# Sensor_module.net
KiCad netlist of a schematic drawn in EAGLE
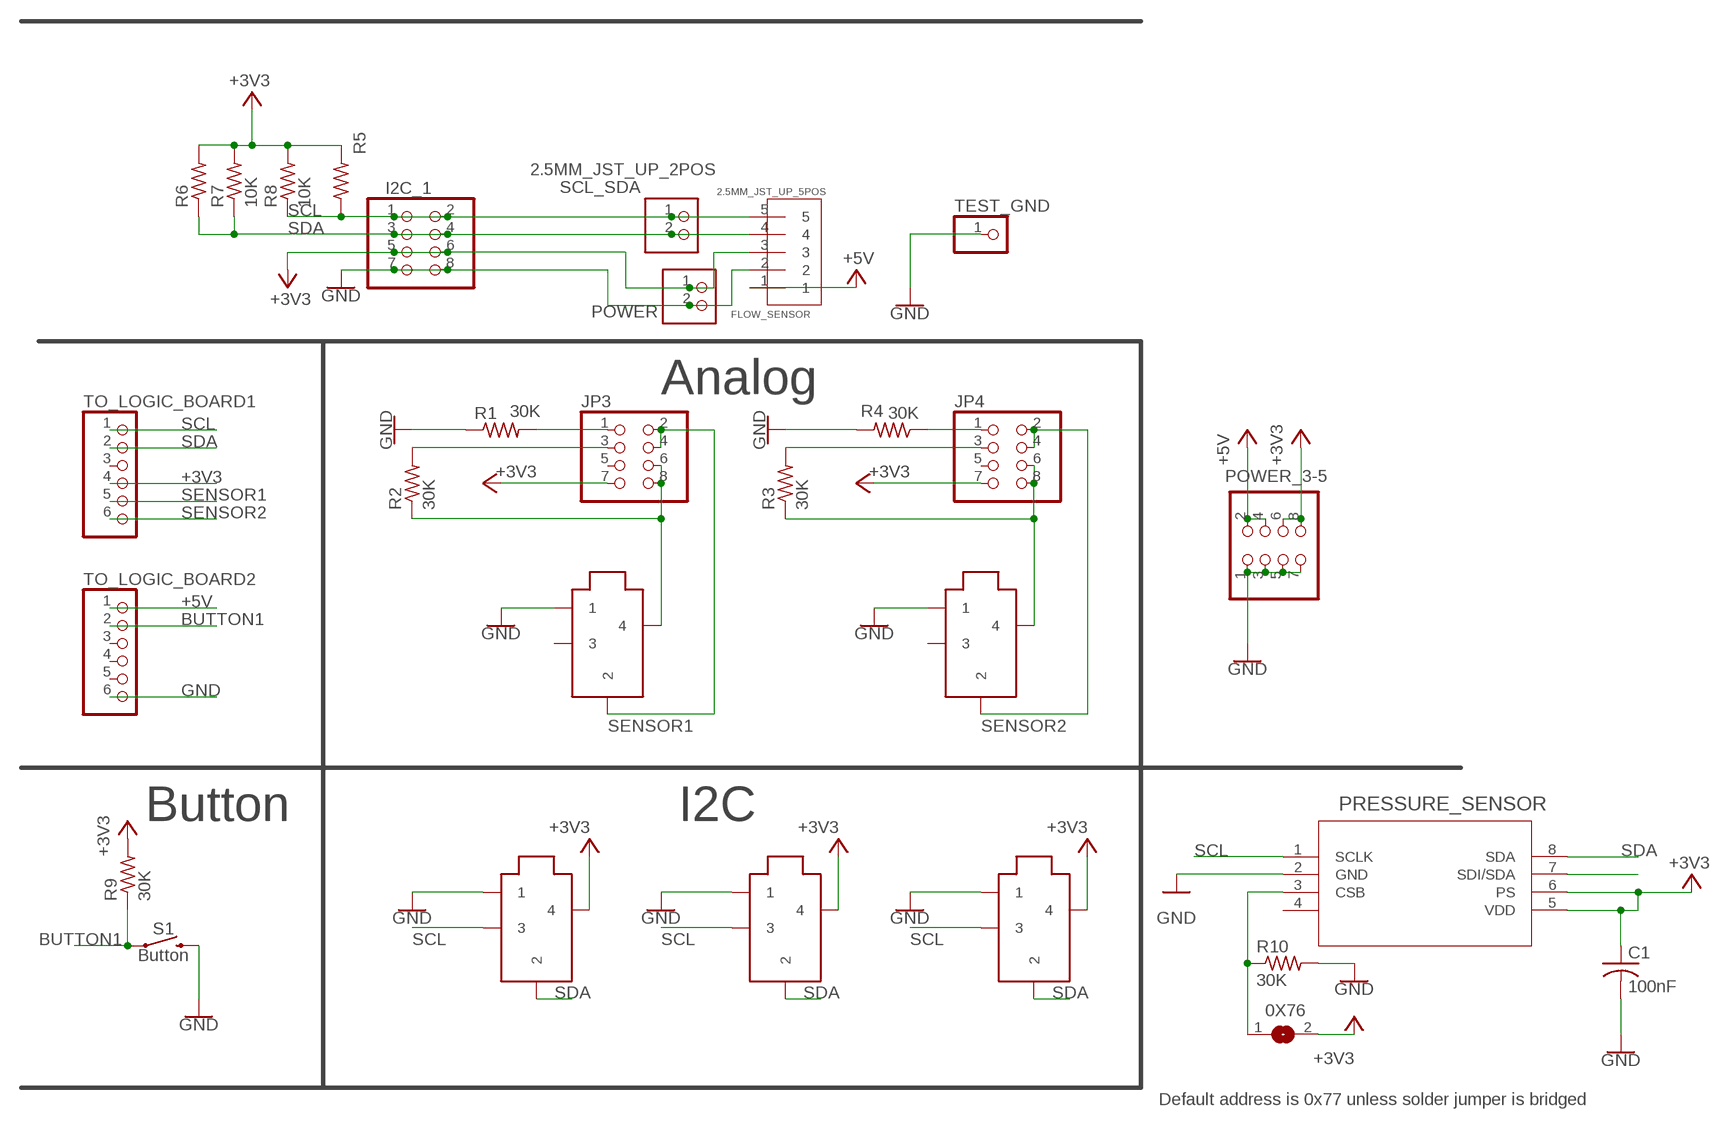
[diagram p0: schematic, sheet 1]

(export (version "E")
  (design (tool "Eeschema 10.0.6"))
  (components
    (comp (ref "0X76")
      (value "SJ")
      (footprint "eagle-import:SJ")
      (libsource (lib "eagle-import") (part "SJ"))
    )
    (comp (ref "ANALOG1")
      (value "AUDIOJACK_2.5MM_SMD")
      (footprint "eagle-import:AJ_2.5_SMD")
      (libsource (lib "eagle-import") (part "AUDIOJACK_2.5MM_SMD"))
    )
    (comp (ref "ANALOG2")
      (value "AUDIOJACK_2.5MM_SMD")
      (footprint "eagle-import:AJ_2.5_SMD")
      (libsource (lib "eagle-import") (part "AUDIOJACK_2.5MM_SMD"))
    )
    (comp (ref "C1")
      (value "100nF")
      (footprint "eagle-import:C1206")
      (libsource (lib "eagle-import") (part "C-USC1206"))
    )
    (comp (ref "FLOW_SENSOR")
      (value "2.5MM_JST_UP_5POS")
      (footprint "eagle-import:JST_5POS_2.5MM_UP")
      (libsource (lib "eagle-import") (part "2.5MM_JST_UP_5POS"))
    )
    (comp (ref "I2C_1")
      (value "PINHD-2X4")
      (footprint "eagle-import:2X04")
      (libsource (lib "eagle-import") (part "PINHD-2X4"))
    )
    (comp (ref "JP3")
      (value "PINHD-2X4")
      (footprint "eagle-import:2X04")
      (libsource (lib "eagle-import") (part "PINHD-2X4"))
    )
    (comp (ref "JP4")
      (value "PINHD-2X4")
      (footprint "eagle-import:2X04")
      (libsource (lib "eagle-import") (part "PINHD-2X4"))
    )
    (comp (ref "POWER")
      (value "2.5MM_JST_UP_2POS")
      (footprint "eagle-import:JST_2POS_2.5MM_UP")
      (libsource (lib "eagle-import") (part "2.5MM_JST_UP_2POS"))
    )
    (comp (ref "POWER_3-5")
      (value "PINHD-2X4")
      (footprint "eagle-import:2X04")
      (libsource (lib "eagle-import") (part "PINHD-2X4"))
    )
    (comp (ref "PRESSURE_SENSOR")
      (value "MS580302BA01-00")
      (footprint "eagle-import:MS5803-02BA01")
      (fields (field (name "MANUFACTURER_PART_NUMBER") "MS580302BA0100"))
      (libsource (lib "eagle-import") (part "MS580302BA01-00"))
    )
    (comp (ref "R1")
      (value "30K")
      (footprint "eagle-import:R1206")
      (libsource (lib "eagle-import") (part "R-US_R1206"))
    )
    (comp (ref "R2")
      (value "30K")
      (footprint "eagle-import:R1206")
      (libsource (lib "eagle-import") (part "R-US_R1206"))
    )
    (comp (ref "R3")
      (value "30K")
      (footprint "eagle-import:R1206")
      (libsource (lib "eagle-import") (part "R-US_R1206"))
    )
    (comp (ref "R4")
      (value "30K")
      (footprint "eagle-import:R1206")
      (libsource (lib "eagle-import") (part "R-US_R1206"))
    )
    (comp (ref "R5")
      (value "R-US_R1206")
      (footprint "eagle-import:R1206")
      (libsource (lib "eagle-import") (part "R-US_R1206"))
    )
    (comp (ref "R6")
      (value "R-US_R1206")
      (footprint "eagle-import:R1206")
      (libsource (lib "eagle-import") (part "R-US_R1206"))
    )
    (comp (ref "R7")
      (value "10K")
      (footprint "eagle-import:0204_7")
      (libsource (lib "eagle-import") (part "R-US_0204/7"))
    )
    (comp (ref "R8")
      (value "10K")
      (footprint "eagle-import:0204_7")
      (libsource (lib "eagle-import") (part "R-US_0204/7"))
    )
    (comp (ref "R9")
      (value "30K")
      (footprint "eagle-import:R1206")
      (libsource (lib "eagle-import") (part "R-US_R1206"))
    )
    (comp (ref "R10")
      (value "30K")
      (footprint "eagle-import:R1206")
      (libsource (lib "eagle-import") (part "R-US_R1206"))
    )
    (comp (ref "S1")
      (value "Button")
      (footprint "eagle-import:TACTILE_SWITCH_PTH_6.0MM")
      (libsource (lib "eagle-import") (part "MOMENTARY-SWITCH-SPST-PTH-6.0MM"))
    )
    (comp (ref "SCL_SDA")
      (value "2.5MM_JST_UP_2POS")
      (footprint "eagle-import:JST_2POS_2.5MM_UP")
      (libsource (lib "eagle-import") (part "2.5MM_JST_UP_2POS"))
    )
    (comp (ref "TEST_GND")
      (value "PINHD-1X1")
      (footprint "eagle-import:1X01")
      (libsource (lib "eagle-import") (part "PINHD-1X1"))
    )
    (comp (ref "TO_LOGIC_BOARD1")
      (value "PINHD-1X6CB")
      (footprint "eagle-import:1X06-CLEANBIG")
      (libsource (lib "eagle-import") (part "PINHD-1X6CB"))
    )
    (comp (ref "TO_LOGIC_BOARD2")
      (value "PINHD-1X6CB")
      (footprint "eagle-import:1X06-CLEANBIG")
      (libsource (lib "eagle-import") (part "PINHD-1X6CB"))
    )
    (comp (ref "U$1")
      (value "I2C")
      (footprint "eagle-import:AJ_2.5_SMD")
      (libsource (lib "eagle-import") (part "AUDIOJACK_2.5MM_SMD"))
    )
    (comp (ref "U$2")
      (value "I2C")
      (footprint "eagle-import:AJ_2.5_SMD")
      (libsource (lib "eagle-import") (part "AUDIOJACK_2.5MM_SMD"))
    )
    (comp (ref "U$5")
      (value "I2C")
      (footprint "eagle-import:AJ_2.5_SMD")
      (libsource (lib "eagle-import") (part "AUDIOJACK_2.5MM_SMD"))
    )
  )
  (nets
    (net (code "1") (name "+3V3") (class "Default")
      (node (ref "0X76") (pin "2") (pinfunction "2_2") (pintype "passive"))
      (node (ref "C1") (pin "1") (pinfunction "1_1") (pintype "passive"))
      (node (ref "FLOW_SENSOR") (pin "3") (pinfunction "3_3") (pintype "bidirectional"))
      (node (ref "I2C_1") (pin "5") (pinfunction "5_5") (pintype "passive"))
      (node (ref "I2C_1") (pin "6") (pinfunction "6_6") (pintype "passive"))
      (node (ref "JP3") (pin "7") (pinfunction "7_7") (pintype "passive"))
      (node (ref "JP4") (pin "7") (pinfunction "7_7") (pintype "passive"))
      (node (ref "POWER") (pin "1") (pinfunction "1_1") (pintype "bidirectional"))
      (node (ref "POWER_3-5") (pin "6") (pinfunction "6_6") (pintype "passive"))
      (node (ref "POWER_3-5") (pin "8") (pinfunction "8_8") (pintype "passive"))
      (node (ref "PRESSURE_SENSOR") (pin "5") (pinfunction "VDD_5") (pintype "power_in"))
      (node (ref "PRESSURE_SENSOR") (pin "6") (pinfunction "PS_6") (pintype "input"))
      (node (ref "R5") (pin "2") (pinfunction "2_2") (pintype "passive"))
      (node (ref "R6") (pin "2") (pinfunction "2_2") (pintype "passive"))
      (node (ref "R7") (pin "2") (pinfunction "2_2") (pintype "passive"))
      (node (ref "R8") (pin "2") (pinfunction "2_2") (pintype "passive"))
      (node (ref "R9") (pin "2") (pinfunction "2_2") (pintype "passive"))
      (node (ref "TO_LOGIC_BOARD1") (pin "4") (pinfunction "4_4") (pintype "passive"))
      (node (ref "U$1") (pin "4") (pinfunction "4_4") (pintype "bidirectional"))
      (node (ref "U$2") (pin "4") (pinfunction "4_4") (pintype "bidirectional"))
      (node (ref "U$5") (pin "4") (pinfunction "4_4") (pintype "bidirectional"))
    )
    (net (code "2") (name "+5V") (class "Default")
      (node (ref "FLOW_SENSOR") (pin "1") (pinfunction "1_1") (pintype "bidirectional"))
      (node (ref "POWER_3-5") (pin "2") (pinfunction "2_2") (pintype "passive"))
      (node (ref "POWER_3-5") (pin "4") (pinfunction "4_4") (pintype "passive"))
      (node (ref "TO_LOGIC_BOARD2") (pin "1") (pinfunction "1_1") (pintype "passive"))
    )
    (net (code "3") (name "/BUTTON1") (class "Default")
      (node (ref "R9") (pin "1") (pinfunction "1_1") (pintype "passive"))
      (node (ref "S1") (pin "1") (pinfunction "1_1") (pintype "passive"))
      (node (ref "TO_LOGIC_BOARD2") (pin "2") (pinfunction "2_2") (pintype "passive"))
    )
    (net (code "4") (name "/SCL") (class "Default")
      (node (ref "FLOW_SENSOR") (pin "5") (pinfunction "5_5") (pintype "bidirectional"))
      (node (ref "I2C_1") (pin "1") (pinfunction "1_1") (pintype "passive"))
      (node (ref "I2C_1") (pin "2") (pinfunction "2_2") (pintype "passive"))
      (node (ref "PRESSURE_SENSOR") (pin "1") (pinfunction "SCLK_1") (pintype "input"))
      (node (ref "R5") (pin "1") (pinfunction "1_1") (pintype "passive"))
      (node (ref "R8") (pin "1") (pinfunction "1_1") (pintype "passive"))
      (node (ref "SCL_SDA") (pin "1") (pinfunction "1_1") (pintype "bidirectional"))
      (node (ref "TO_LOGIC_BOARD1") (pin "1") (pinfunction "1_1") (pintype "passive"))
      (node (ref "U$1") (pin "3") (pinfunction "3_3") (pintype "bidirectional"))
      (node (ref "U$2") (pin "3") (pinfunction "3_3") (pintype "bidirectional"))
      (node (ref "U$5") (pin "3") (pinfunction "3_3") (pintype "bidirectional"))
    )
    (net (code "5") (name "/SDA") (class "Default")
      (node (ref "FLOW_SENSOR") (pin "4") (pinfunction "4_4") (pintype "bidirectional"))
      (node (ref "I2C_1") (pin "3") (pinfunction "3_3") (pintype "passive"))
      (node (ref "I2C_1") (pin "4") (pinfunction "4_4") (pintype "passive"))
      (node (ref "PRESSURE_SENSOR") (pin "8") (pinfunction "SDA_8") (pintype "output"))
      (node (ref "R6") (pin "1") (pinfunction "1_1") (pintype "passive"))
      (node (ref "R7") (pin "1") (pinfunction "1_1") (pintype "passive"))
      (node (ref "SCL_SDA") (pin "2") (pinfunction "2_2") (pintype "bidirectional"))
      (node (ref "TO_LOGIC_BOARD1") (pin "2") (pinfunction "2_2") (pintype "passive"))
      (node (ref "U$1") (pin "2") (pinfunction "2_2") (pintype "bidirectional"))
      (node (ref "U$2") (pin "2") (pinfunction "2_2") (pintype "bidirectional"))
      (node (ref "U$5") (pin "2") (pinfunction "2_2") (pintype "bidirectional"))
    )
    (net (code "6") (name "/SENSOR1") (class "Default")
      (node (ref "ANALOG1") (pin "2") (pinfunction "2_2") (pintype "bidirectional"))
      (node (ref "JP3") (pin "2") (pinfunction "2_2") (pintype "passive"))
      (node (ref "JP3") (pin "4") (pinfunction "4_4") (pintype "passive"))
      (node (ref "TO_LOGIC_BOARD1") (pin "5") (pinfunction "5_5") (pintype "passive"))
    )
    (net (code "7") (name "/SENSOR2") (class "Default")
      (node (ref "ANALOG2") (pin "2") (pinfunction "2_2") (pintype "bidirectional"))
      (node (ref "JP4") (pin "2") (pinfunction "2_2") (pintype "passive"))
      (node (ref "JP4") (pin "4") (pinfunction "4_4") (pintype "passive"))
      (node (ref "TO_LOGIC_BOARD1") (pin "6") (pinfunction "6_6") (pintype "passive"))
    )
    (net (code "8") (name "GND") (class "Default")
      (node (ref "ANALOG1") (pin "1") (pinfunction "1_1") (pintype "bidirectional"))
      (node (ref "ANALOG2") (pin "1") (pinfunction "1_1") (pintype "bidirectional"))
      (node (ref "C1") (pin "2") (pinfunction "2_2") (pintype "passive"))
      (node (ref "FLOW_SENSOR") (pin "2") (pinfunction "2_2") (pintype "bidirectional"))
      (node (ref "I2C_1") (pin "7") (pinfunction "7_7") (pintype "passive"))
      (node (ref "I2C_1") (pin "8") (pinfunction "8_8") (pintype "passive"))
      (node (ref "POWER") (pin "2") (pinfunction "2_2") (pintype "bidirectional"))
      (node (ref "POWER_3-5") (pin "1") (pinfunction "1_1") (pintype "passive"))
      (node (ref "POWER_3-5") (pin "3") (pinfunction "3_3") (pintype "passive"))
      (node (ref "POWER_3-5") (pin "5") (pinfunction "5_5") (pintype "passive"))
      (node (ref "POWER_3-5") (pin "7") (pinfunction "7_7") (pintype "passive"))
      (node (ref "PRESSURE_SENSOR") (pin "2") (pinfunction "GND_2") (pintype "passive"))
      (node (ref "R1") (pin "1") (pinfunction "1_1") (pintype "passive"))
      (node (ref "R10") (pin "2") (pinfunction "2_2") (pintype "passive"))
      (node (ref "R4") (pin "2") (pinfunction "2_2") (pintype "passive"))
      (node (ref "S1") (pin "3") (pinfunction "2_3") (pintype "passive"))
      (node (ref "TEST_GND") (pin "1") (pinfunction "1_1") (pintype "passive"))
      (node (ref "TO_LOGIC_BOARD2") (pin "6") (pinfunction "6_6") (pintype "passive"))
      (node (ref "U$1") (pin "1") (pinfunction "1_1") (pintype "bidirectional"))
      (node (ref "U$2") (pin "1") (pinfunction "1_1") (pintype "bidirectional"))
      (node (ref "U$5") (pin "1") (pinfunction "1_1") (pintype "bidirectional"))
    )
    (net (code "9") (name "Net-(ANALOG1-Pad4)") (class "Default")
      (node (ref "ANALOG1") (pin "4") (pinfunction "4_4") (pintype "bidirectional"))
      (node (ref "JP3") (pin "6") (pinfunction "6_6") (pintype "passive"))
      (node (ref "JP3") (pin "8") (pinfunction "8_8") (pintype "passive"))
      (node (ref "R2") (pin "1") (pinfunction "1_1") (pintype "passive"))
    )
    (net (code "10") (name "Net-(ANALOG2-Pad4)") (class "Default")
      (node (ref "ANALOG2") (pin "4") (pinfunction "4_4") (pintype "bidirectional"))
      (node (ref "JP4") (pin "6") (pinfunction "6_6") (pintype "passive"))
      (node (ref "JP4") (pin "8") (pinfunction "8_8") (pintype "passive"))
      (node (ref "R3") (pin "1") (pinfunction "1_1") (pintype "passive"))
    )
    (net (code "11") (name "Net-(JP3-Pad1)") (class "Default")
      (node (ref "JP3") (pin "1") (pinfunction "1_1") (pintype "passive"))
      (node (ref "R1") (pin "2") (pinfunction "2_2") (pintype "passive"))
    )
    (net (code "12") (name "Net-(JP3-Pad3)") (class "Default")
      (node (ref "JP3") (pin "3") (pinfunction "3_3") (pintype "passive"))
      (node (ref "R2") (pin "2") (pinfunction "2_2") (pintype "passive"))
    )
    (net (code "13") (name "Net-(JP4-Pad1)") (class "Default")
      (node (ref "JP4") (pin "1") (pinfunction "1_1") (pintype "passive"))
      (node (ref "R4") (pin "1") (pinfunction "1_1") (pintype "passive"))
    )
    (net (code "14") (name "Net-(JP4-Pad3)") (class "Default")
      (node (ref "JP4") (pin "3") (pinfunction "3_3") (pintype "passive"))
      (node (ref "R3") (pin "2") (pinfunction "2_2") (pintype "passive"))
    )
    (net (code "15") (name "Net-(PRESSURE_SENSOR-CSB)") (class "Default")
      (node (ref "0X76") (pin "1") (pinfunction "1_1") (pintype "passive"))
      (node (ref "PRESSURE_SENSOR") (pin "3") (pinfunction "CSB_3") (pintype "input"))
      (node (ref "R10") (pin "1") (pinfunction "1_1") (pintype "passive"))
    )
    (net (code "16") (name "unconnected-(ANALOG1-Pad3)") (class "Default")
      (node (ref "ANALOG1") (pin "3") (pinfunction "3_3") (pintype "bidirectional"))
    )
    (net (code "17") (name "unconnected-(ANALOG2-Pad3)") (class "Default")
      (node (ref "ANALOG2") (pin "3") (pinfunction "3_3") (pintype "bidirectional"))
    )
    (net (code "18") (name "unconnected-(JP3-Pad5)") (class "Default")
      (node (ref "JP3") (pin "5") (pinfunction "5_5") (pintype "passive"))
    )
    (net (code "19") (name "unconnected-(JP4-Pad5)") (class "Default")
      (node (ref "JP4") (pin "5") (pinfunction "5_5") (pintype "passive"))
    )
    (net (code "20") (name "unconnected-(PRESSURE_SENSOR-NC-Pad4)") (class "Default")
      (node (ref "PRESSURE_SENSOR") (pin "4") (pinfunction "NC_4") (pintype "no_connect"))
    )
    (net (code "21") (name "unconnected-(PRESSURE_SENSOR-SDI{slash}SDA-Pad7)") (class "Default")
      (node (ref "PRESSURE_SENSOR") (pin "7") (pinfunction "SDI/SDA_7") (pintype "input"))
    )
    (net (code "22") (name "unconnected-(TO_LOGIC_BOARD1-Pad3)") (class "Default")
      (node (ref "TO_LOGIC_BOARD1") (pin "3") (pinfunction "3_3") (pintype "passive"))
    )
    (net (code "23") (name "unconnected-(TO_LOGIC_BOARD2-Pad3)") (class "Default")
      (node (ref "TO_LOGIC_BOARD2") (pin "3") (pinfunction "3_3") (pintype "passive"))
    )
    (net (code "24") (name "unconnected-(TO_LOGIC_BOARD2-Pad4)") (class "Default")
      (node (ref "TO_LOGIC_BOARD2") (pin "4") (pinfunction "4_4") (pintype "passive"))
    )
    (net (code "25") (name "unconnected-(TO_LOGIC_BOARD2-Pad5)") (class "Default")
      (node (ref "TO_LOGIC_BOARD2") (pin "5") (pinfunction "5_5") (pintype "passive"))
    )
  )
)
